# Fonte.net
KiCad netlist of a schematic drawn in EAGLE
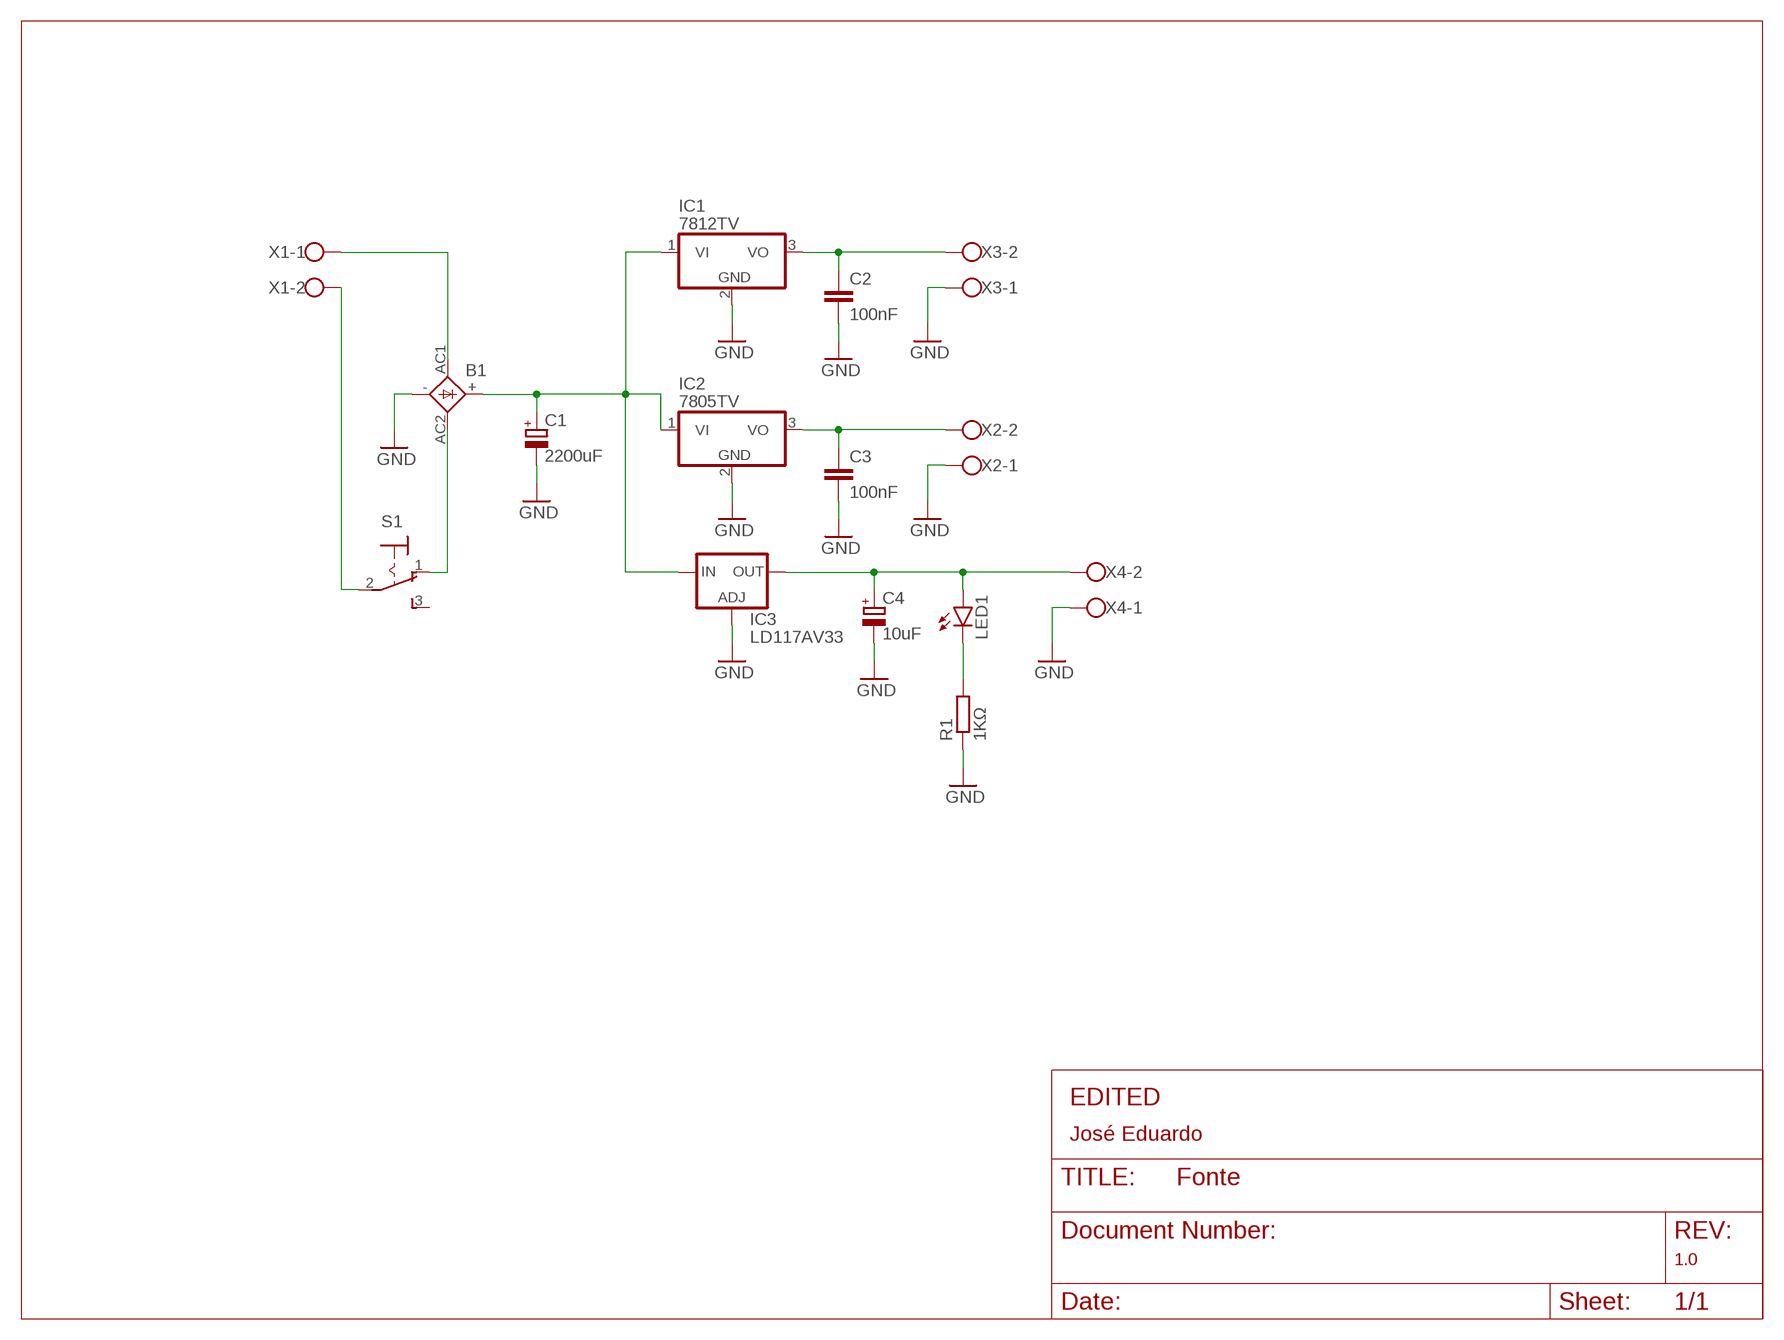
[diagram p0: schematic, sheet 1]

(export (version "E")
  (design (tool "Eeschema 10.0.6"))
  (components
    (comp (ref "B1")
      (value "2KBB")
      (footprint "eagle-import:2KBB")
      (libsource (lib "eagle-import") (part "2KBB"))
    )
    (comp (ref "C1")
      (value "2200uF")
      (footprint "eagle-import:E5-13")
      (libsource (lib "eagle-import") (part "resistor_348_CPOL-EUE5-13"))
    )
    (comp (ref "C2")
      (value "100nF")
      (footprint "eagle-import:C025-024X044")
      (libsource (lib "eagle-import") (part "C-EU025-024X044"))
    )
    (comp (ref "C3")
      (value "100nF")
      (footprint "eagle-import:C025-024X044")
      (libsource (lib "eagle-import") (part "C-EU025-024X044"))
    )
    (comp (ref "C4")
      (value "10uF")
      (footprint "eagle-import:E1,8-4")
      (libsource (lib "eagle-import") (part "CPOL-EUE1.8-4"))
    )
    (comp (ref "IC1")
      (value "7812TV")
      (footprint "eagle-import:TO220V")
      (libsource (lib "eagle-import") (part "78TV12"))
    )
    (comp (ref "IC2")
      (value "7805TV")
      (footprint "eagle-import:TO220V")
      (libsource (lib "eagle-import") (part "78TV05"))
    )
    (comp (ref "IC3")
      (value "LD117AV33")
      (footprint "eagle-import:TO220S")
      (libsource (lib "eagle-import") (part "LD117A?V33"))
    )
    (comp (ref "LED1")
      (value "LED5MM")
      (footprint "eagle-import:LED5MM")
      (libsource (lib "eagle-import") (part "LED5MM"))
    )
    (comp (ref "R1")
      (value "1KΩ")
      (footprint "eagle-import:0207_10")
      (libsource (lib "eagle-import") (part "R-EU_0207/10"))
    )
    (comp (ref "S1")
      (value "M9040P")
      (footprint "eagle-import:M9040P")
      (libsource (lib "eagle-import") (part "M9040P"))
    )
    (comp (ref "X1")
      (value "W237-102")
      (footprint "eagle-import:W237-102")
      (fields (field (name "MPN") "237-102"))
      (libsource (lib "eagle-import") (part "W237-102"))
    )
    (comp (ref "X2")
      (value "W237-102")
      (footprint "eagle-import:W237-102")
      (fields (field (name "MPN") "237-102"))
      (libsource (lib "eagle-import") (part "W237-102"))
    )
    (comp (ref "X3")
      (value "W237-102")
      (footprint "eagle-import:W237-102")
      (fields (field (name "MPN") "237-102"))
      (libsource (lib "eagle-import") (part "W237-102"))
    )
    (comp (ref "X4")
      (value "W237-102")
      (footprint "eagle-import:W237-102")
      (fields (field (name "MPN") "237-102"))
      (libsource (lib "eagle-import") (part "W237-102"))
    )
  )
  (nets
    (net (code "1") (name "GND") (class "Default")
      (node (ref "B1") (pin "-") (pinfunction "-_-") (pintype "passive"))
      (node (ref "C1") (pin "-") (pinfunction "-_-") (pintype "passive"))
      (node (ref "C2") (pin "2") (pinfunction "2_2") (pintype "passive"))
      (node (ref "C3") (pin "2") (pinfunction "2_2") (pintype "passive"))
      (node (ref "C4") (pin "-") (pinfunction "-_-") (pintype "passive"))
      (node (ref "IC1") (pin "2") (pinfunction "GND_2") (pintype "passive"))
      (node (ref "IC2") (pin "2") (pinfunction "GND_2") (pintype "passive"))
      (node (ref "IC3") (pin "1") (pinfunction "ADJ_1") (pintype "input"))
      (node (ref "R1") (pin "1") (pinfunction "1_1") (pintype "passive"))
      (node (ref "X2") (pin "1") (pinfunction "KL_1") (pintype "passive"))
      (node (ref "X3") (pin "1") (pinfunction "KL_1") (pintype "passive"))
      (node (ref "X4") (pin "1") (pinfunction "KL_1") (pintype "passive"))
    )
    (net (code "2") (name "Net-(IC1-VI)") (class "Default")
      (node (ref "B1") (pin "+") (pinfunction "+_+") (pintype "passive"))
      (node (ref "C1") (pin "+") (pinfunction "+_+") (pintype "passive"))
      (node (ref "IC1") (pin "1") (pinfunction "VI_1") (pintype "input"))
      (node (ref "IC2") (pin "1") (pinfunction "VI_1") (pintype "input"))
      (node (ref "IC3") (pin "3") (pinfunction "IN_3") (pintype "input"))
    )
    (net (code "3") (name "Net-(IC1-VO)") (class "Default")
      (node (ref "C2") (pin "1") (pinfunction "1_1") (pintype "passive"))
      (node (ref "IC1") (pin "3") (pinfunction "VO_3") (pintype "passive"))
      (node (ref "X3") (pin "2") (pinfunction "KL_2") (pintype "passive"))
    )
    (net (code "4") (name "Net-(IC2-VO)") (class "Default")
      (node (ref "C3") (pin "1") (pinfunction "1_1") (pintype "passive"))
      (node (ref "IC2") (pin "3") (pinfunction "VO_3") (pintype "passive"))
      (node (ref "X2") (pin "2") (pinfunction "KL_2") (pintype "passive"))
    )
    (net (code "5") (name "Net-(IC3-OUT)") (class "Default")
      (node (ref "C4") (pin "+") (pinfunction "+_+") (pintype "passive"))
      (node (ref "IC3") (pin "2") (pinfunction "OUT_2") (pintype "passive"))
      (node (ref "LED1") (pin "A") (pinfunction "A_A") (pintype "passive"))
      (node (ref "X4") (pin "2") (pinfunction "KL_2") (pintype "passive"))
    )
    (net (code "6") (name "Net-(LED1-C)") (class "Default")
      (node (ref "LED1") (pin "K") (pinfunction "C_K") (pintype "passive"))
      (node (ref "R1") (pin "2") (pinfunction "2_2") (pintype "passive"))
    )
    (net (code "7") (name "Net-(S1-O)") (class "Default")
      (node (ref "B1") (pin "AC2") (pinfunction "AC2_AC2") (pintype "passive"))
      (node (ref "S1") (pin "1") (pinfunction "O_1") (pintype "passive"))
    )
    (net (code "8") (name "Net-(S1-P)") (class "Default")
      (node (ref "S1") (pin "2") (pinfunction "P_2") (pintype "passive"))
      (node (ref "X1") (pin "2") (pinfunction "KL_2") (pintype "passive"))
    )
    (net (code "9") (name "Net-(X1A-KL)") (class "Default")
      (node (ref "B1") (pin "AC1") (pinfunction "AC1_AC1") (pintype "passive"))
      (node (ref "X1") (pin "1") (pinfunction "KL_1") (pintype "passive"))
    )
    (net (code "10") (name "unconnected-(S1-S-Pad3)") (class "Default")
      (node (ref "S1") (pin "3") (pinfunction "S_3") (pintype "passive"))
    )
  )
)
